# Xbee_Footprint_--_BLE_--_HM-10_--_Breako.net
KiCad netlist of a schematic drawn in EAGLE
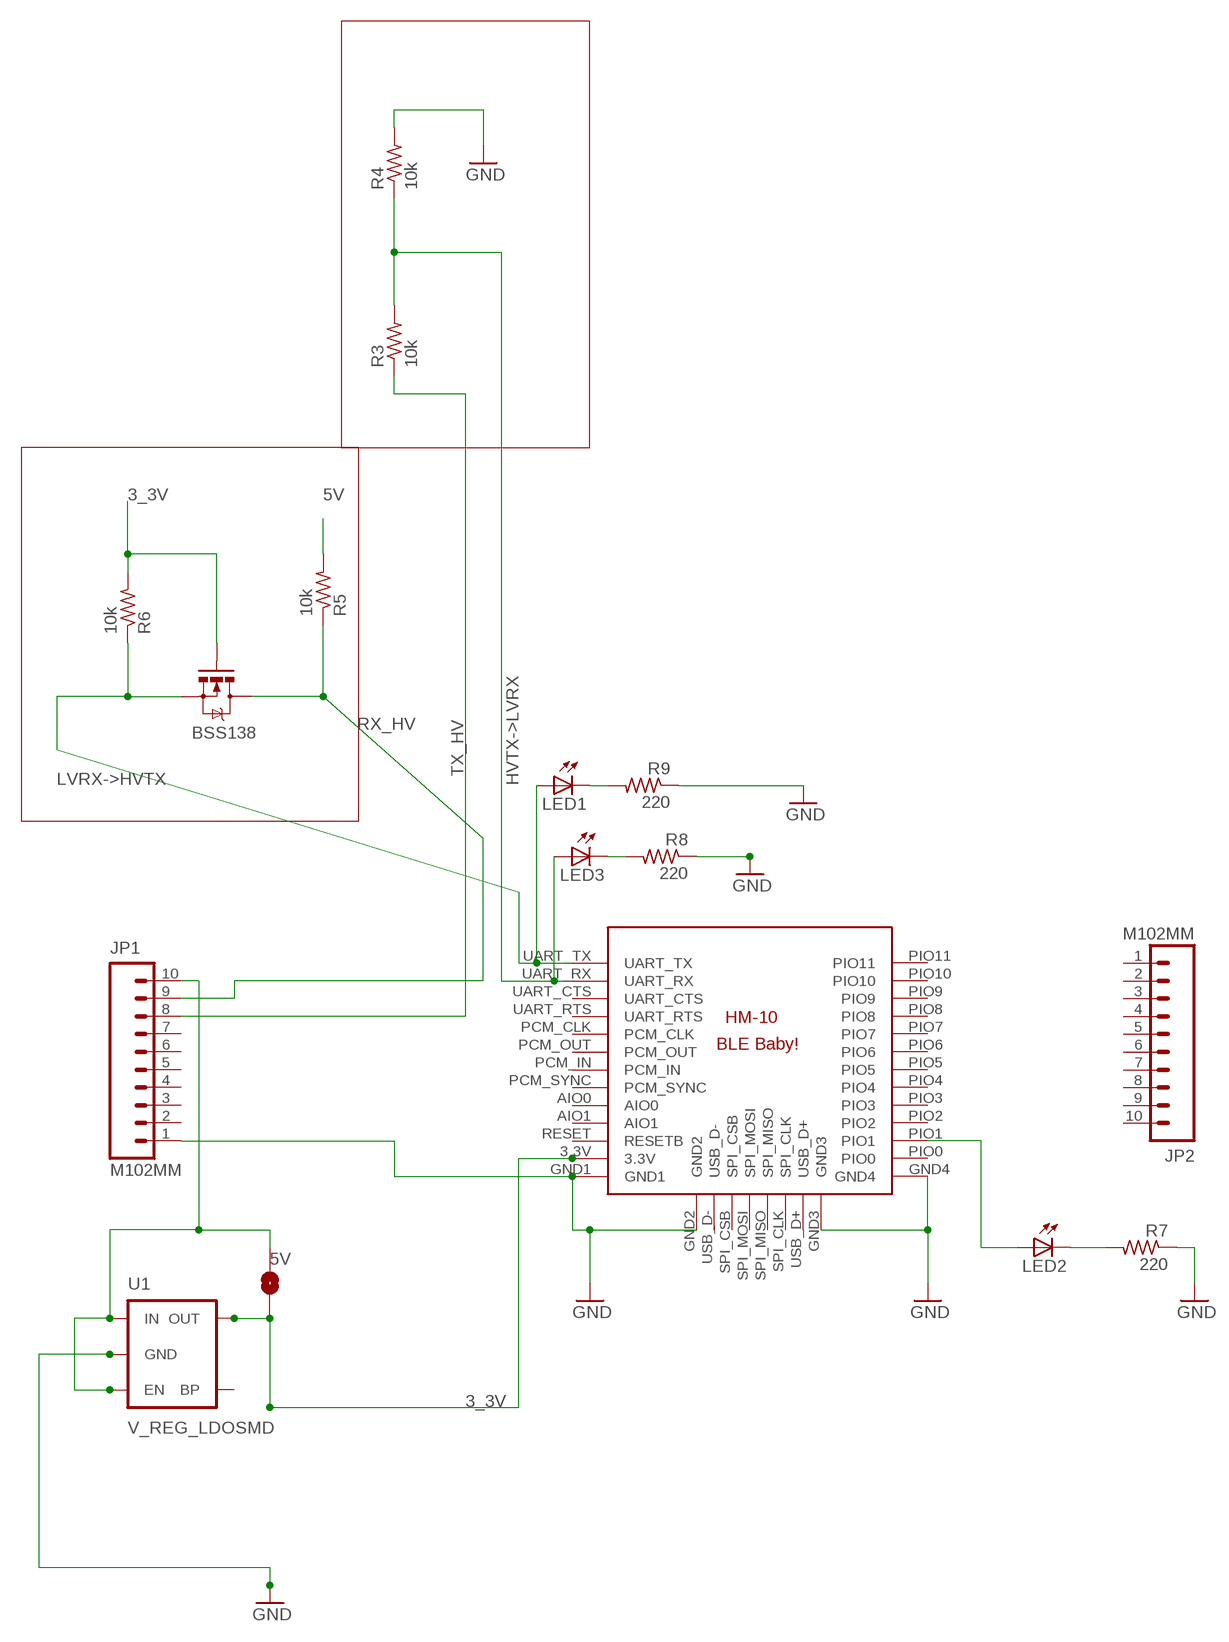
[diagram p0: schematic, sheet 1]

(export (version "E")
  (design (tool "Eeschema 10.0.6"))
  (components
    (comp (ref "BSS138")
      (value "MOSFET-NCHANNELSMD")
      (footprint "eagle-import:SOT23-3")
      (libsource (lib "eagle-import") (part "MOSFET-NCHANNELSMD"))
    )
    (comp (ref "JP1")
      (value "M102MM")
      (footprint "eagle-import:1X10-2MM")
      (libsource (lib "eagle-import") (part "M102MM"))
    )
    (comp (ref "JP2")
      (value "M102MM")
      (footprint "eagle-import:1X10-2MM")
      (libsource (lib "eagle-import") (part "M102MM"))
    )
    (comp (ref "LED1")
      (value "LED0603")
      (footprint "eagle-import:LED-0603")
      (libsource (lib "eagle-import") (part "LED0603"))
    )
    (comp (ref "LED2")
      (value "LED0603")
      (footprint "eagle-import:LED-0603")
      (libsource (lib "eagle-import") (part "LED0603"))
    )
    (comp (ref "LED3")
      (value "LED0603")
      (footprint "eagle-import:LED-0603")
      (libsource (lib "eagle-import") (part "LED0603"))
    )
    (comp (ref "R3")
      (value "10k")
      (footprint "eagle-import:M0805")
      (libsource (lib "eagle-import") (part "R-US_M0805"))
    )
    (comp (ref "R4")
      (value "10k")
      (footprint "eagle-import:M0805")
      (libsource (lib "eagle-import") (part "R-US_M0805"))
    )
    (comp (ref "R5")
      (value "10k")
      (footprint "eagle-import:M0805")
      (libsource (lib "eagle-import") (part "R-US_M0805"))
    )
    (comp (ref "R6")
      (value "10k")
      (footprint "eagle-import:M0805")
      (libsource (lib "eagle-import") (part "R-US_M0805"))
    )
    (comp (ref "R7")
      (value "220")
      (footprint "eagle-import:M0805")
      (libsource (lib "eagle-import") (part "R-US_M0805"))
    )
    (comp (ref "R8")
      (value "220")
      (footprint "eagle-import:M0805")
      (libsource (lib "eagle-import") (part "R-US_M0805"))
    )
    (comp (ref "R9")
      (value "220")
      (footprint "eagle-import:M0805")
      (libsource (lib "eagle-import") (part "R-US_M0805"))
    )
    (comp (ref "SJ1")
      (value "SOLDERJUMPERNO")
      (footprint "eagle-import:SJ_2S-NO")
      (libsource (lib "eagle-import") (part "SOLDERJUMPERNO"))
    )
    (comp (ref "U$1")
      (value "BLE-HM-10")
      (footprint "eagle-import:BLE-HM-10")
      (libsource (lib "eagle-import") (part "BLE-HM-10"))
    )
    (comp (ref "U1")
      (value "V_REG_LDOSMD")
      (footprint "eagle-import:SOT23-5")
      (libsource (lib "eagle-import") (part "V_REG_LDOSMD"))
    )
  )
  (nets
    (net (code "1") (name "/3_3V") (class "Default")
      (node (ref "BSS138") (pin "1") (pinfunction "G_1") (pintype "passive"))
      (node (ref "R6") (pin "2") (pinfunction "2_2") (pintype "passive"))
      (node (ref "SJ1") (pin "1") (pinfunction "1_1") (pintype "passive"))
      (node (ref "U$1") (pin "3.3V") (pinfunction "3.3V_3.3V") (pintype "bidirectional"))
      (node (ref "U1") (pin "5") (pinfunction "OUT_5") (pintype "passive"))
    )
    (net (code "2") (name "/5V") (class "Default")
      (node (ref "JP1") (pin "10") (pinfunction "10_10") (pintype "passive"))
      (node (ref "R5") (pin "2") (pinfunction "2_2") (pintype "passive"))
      (node (ref "SJ1") (pin "2") (pinfunction "2_2") (pintype "passive"))
      (node (ref "U1") (pin "1") (pinfunction "IN_1") (pintype "input"))
      (node (ref "U1") (pin "3") (pinfunction "EN_3") (pintype "input"))
    )
    (net (code "3") (name "/HVTX->LVRX") (class "Default")
      (node (ref "LED3") (pin "A") (pinfunction "A_A") (pintype "passive"))
      (node (ref "R3") (pin "2") (pinfunction "2_2") (pintype "passive"))
      (node (ref "R4") (pin "1") (pinfunction "1_1") (pintype "passive"))
      (node (ref "U$1") (pin "UART_RX") (pinfunction "UART_RX_UART_RX") (pintype "bidirectional"))
    )
    (net (code "4") (name "/LVRX->HVTX") (class "Default")
      (node (ref "BSS138") (pin "2") (pinfunction "S_2") (pintype "passive"))
      (node (ref "LED1") (pin "A") (pinfunction "A_A") (pintype "passive"))
      (node (ref "R6") (pin "1") (pinfunction "1_1") (pintype "passive"))
      (node (ref "U$1") (pin "UART_TX") (pinfunction "UART_TX_UART_TX") (pintype "bidirectional"))
    )
    (net (code "5") (name "/RX_HV") (class "Default")
      (node (ref "BSS138") (pin "3") (pinfunction "D_3") (pintype "passive"))
      (node (ref "JP1") (pin "9") (pinfunction "9_9") (pintype "passive"))
      (node (ref "R5") (pin "1") (pinfunction "1_1") (pintype "passive"))
    )
    (net (code "6") (name "/TX_HV") (class "Default")
      (node (ref "JP1") (pin "8") (pinfunction "8_8") (pintype "passive"))
      (node (ref "R3") (pin "1") (pinfunction "1_1") (pintype "passive"))
    )
    (net (code "7") (name "GND") (class "Default")
      (node (ref "JP1") (pin "1") (pinfunction "1_1") (pintype "passive"))
      (node (ref "R4") (pin "2") (pinfunction "2_2") (pintype "passive"))
      (node (ref "R7") (pin "1") (pinfunction "1_1") (pintype "passive"))
      (node (ref "R8") (pin "1") (pinfunction "1_1") (pintype "passive"))
      (node (ref "R9") (pin "1") (pinfunction "1_1") (pintype "passive"))
      (node (ref "U$1") (pin "GND1") (pinfunction "GND1_GND1") (pintype "bidirectional"))
      (node (ref "U$1") (pin "GND2") (pinfunction "GND2_GND2") (pintype "bidirectional"))
      (node (ref "U$1") (pin "GND3") (pinfunction "GND3_GND3") (pintype "bidirectional"))
      (node (ref "U$1") (pin "GND4") (pinfunction "GND4_GND4") (pintype "bidirectional"))
      (node (ref "U1") (pin "2") (pinfunction "GND_2") (pintype "input"))
    )
    (net (code "8") (name "Net-(LED1-PadC)") (class "Default")
      (node (ref "LED1") (pin "C") (pinfunction "C_C") (pintype "passive"))
      (node (ref "R9") (pin "2") (pinfunction "2_2") (pintype "passive"))
    )
    (net (code "9") (name "Net-(LED2-PadA)") (class "Default")
      (node (ref "LED2") (pin "A") (pinfunction "A_A") (pintype "passive"))
      (node (ref "U$1") (pin "PIO1") (pinfunction "PIO1_PIO1") (pintype "bidirectional"))
    )
    (net (code "10") (name "Net-(LED2-PadC)") (class "Default")
      (node (ref "LED2") (pin "C") (pinfunction "C_C") (pintype "passive"))
      (node (ref "R7") (pin "2") (pinfunction "2_2") (pintype "passive"))
    )
    (net (code "11") (name "Net-(LED3-PadC)") (class "Default")
      (node (ref "LED3") (pin "C") (pinfunction "C_C") (pintype "passive"))
      (node (ref "R8") (pin "2") (pinfunction "2_2") (pintype "passive"))
    )
    (net (code "12") (name "unconnected-(JP1-Pad2)") (class "Default")
      (node (ref "JP1") (pin "2") (pinfunction "2_2") (pintype "passive"))
    )
    (net (code "13") (name "unconnected-(JP1-Pad3)") (class "Default")
      (node (ref "JP1") (pin "3") (pinfunction "3_3") (pintype "passive"))
    )
    (net (code "14") (name "unconnected-(JP1-Pad4)") (class "Default")
      (node (ref "JP1") (pin "4") (pinfunction "4_4") (pintype "passive"))
    )
    (net (code "15") (name "unconnected-(JP1-Pad5)") (class "Default")
      (node (ref "JP1") (pin "5") (pinfunction "5_5") (pintype "passive"))
    )
    (net (code "16") (name "unconnected-(JP1-Pad6)") (class "Default")
      (node (ref "JP1") (pin "6") (pinfunction "6_6") (pintype "passive"))
    )
    (net (code "17") (name "unconnected-(JP1-Pad7)") (class "Default")
      (node (ref "JP1") (pin "7") (pinfunction "7_7") (pintype "passive"))
    )
    (net (code "18") (name "unconnected-(JP2-Pad1)") (class "Default")
      (node (ref "JP2") (pin "1") (pinfunction "1_1") (pintype "passive"))
    )
    (net (code "19") (name "unconnected-(JP2-Pad2)") (class "Default")
      (node (ref "JP2") (pin "2") (pinfunction "2_2") (pintype "passive"))
    )
    (net (code "20") (name "unconnected-(JP2-Pad3)") (class "Default")
      (node (ref "JP2") (pin "3") (pinfunction "3_3") (pintype "passive"))
    )
    (net (code "21") (name "unconnected-(JP2-Pad4)") (class "Default")
      (node (ref "JP2") (pin "4") (pinfunction "4_4") (pintype "passive"))
    )
    (net (code "22") (name "unconnected-(JP2-Pad5)") (class "Default")
      (node (ref "JP2") (pin "5") (pinfunction "5_5") (pintype "passive"))
    )
    (net (code "23") (name "unconnected-(JP2-Pad6)") (class "Default")
      (node (ref "JP2") (pin "6") (pinfunction "6_6") (pintype "passive"))
    )
    (net (code "24") (name "unconnected-(JP2-Pad7)") (class "Default")
      (node (ref "JP2") (pin "7") (pinfunction "7_7") (pintype "passive"))
    )
    (net (code "25") (name "unconnected-(JP2-Pad8)") (class "Default")
      (node (ref "JP2") (pin "8") (pinfunction "8_8") (pintype "passive"))
    )
    (net (code "26") (name "unconnected-(JP2-Pad9)") (class "Default")
      (node (ref "JP2") (pin "9") (pinfunction "9_9") (pintype "passive"))
    )
    (net (code "27") (name "unconnected-(JP2-Pad10)") (class "Default")
      (node (ref "JP2") (pin "10") (pinfunction "10_10") (pintype "passive"))
    )
    (net (code "28") (name "unconnected-(U$1-PadAIO0)") (class "Default")
      (node (ref "U$1") (pin "AIO0") (pinfunction "AIO0_AIO0") (pintype "bidirectional"))
    )
    (net (code "29") (name "unconnected-(U$1-PadAIO1)") (class "Default")
      (node (ref "U$1") (pin "AIO1") (pinfunction "AIO1_AIO1") (pintype "bidirectional"))
    )
    (net (code "30") (name "unconnected-(U$1-PadPCM_CLK)") (class "Default")
      (node (ref "U$1") (pin "PCM_CLK") (pinfunction "PCM_CLK_PCM_CLK") (pintype "bidirectional"))
    )
    (net (code "31") (name "unconnected-(U$1-PadPCM_IN)") (class "Default")
      (node (ref "U$1") (pin "PCM_IN") (pinfunction "PCM_IN_PCM_IN") (pintype "bidirectional"))
    )
    (net (code "32") (name "unconnected-(U$1-PadPCM_OUT)") (class "Default")
      (node (ref "U$1") (pin "PCM_OUT") (pinfunction "PCM_OUT_PCM_OUT") (pintype "bidirectional"))
    )
    (net (code "33") (name "unconnected-(U$1-PadPCM_SYNC)") (class "Default")
      (node (ref "U$1") (pin "PCM_SYNC") (pinfunction "PCM_SYNC_PCM_SYNC") (pintype "bidirectional"))
    )
    (net (code "34") (name "unconnected-(U$1-PadPIO0)") (class "Default")
      (node (ref "U$1") (pin "PIO0") (pinfunction "PIO0_PIO0") (pintype "bidirectional"))
    )
    (net (code "35") (name "unconnected-(U$1-PadPIO2)") (class "Default")
      (node (ref "U$1") (pin "PIO2") (pinfunction "PIO2_PIO2") (pintype "bidirectional"))
    )
    (net (code "36") (name "unconnected-(U$1-PadPIO3)") (class "Default")
      (node (ref "U$1") (pin "PIO3") (pinfunction "PIO3_PIO3") (pintype "bidirectional"))
    )
    (net (code "37") (name "unconnected-(U$1-PadPIO4)") (class "Default")
      (node (ref "U$1") (pin "PIO4") (pinfunction "PIO4_PIO4") (pintype "bidirectional"))
    )
    (net (code "38") (name "unconnected-(U$1-PadPIO5)") (class "Default")
      (node (ref "U$1") (pin "PIO5") (pinfunction "PIO5_PIO5") (pintype "bidirectional"))
    )
    (net (code "39") (name "unconnected-(U$1-PadPIO6)") (class "Default")
      (node (ref "U$1") (pin "PIO6") (pinfunction "PIO6_PIO6") (pintype "bidirectional"))
    )
    (net (code "40") (name "unconnected-(U$1-PadPIO7)") (class "Default")
      (node (ref "U$1") (pin "PIO7") (pinfunction "PIO7_PIO7") (pintype "bidirectional"))
    )
    (net (code "41") (name "unconnected-(U$1-PadPIO8)") (class "Default")
      (node (ref "U$1") (pin "PIO8") (pinfunction "PIO8_PIO8") (pintype "bidirectional"))
    )
    (net (code "42") (name "unconnected-(U$1-PadPIO9)") (class "Default")
      (node (ref "U$1") (pin "PIO9") (pinfunction "PIO9_PIO9") (pintype "bidirectional"))
    )
    (net (code "43") (name "unconnected-(U$1-PadPIO10)") (class "Default")
      (node (ref "U$1") (pin "PIO10") (pinfunction "PIO10_PIO10") (pintype "bidirectional"))
    )
    (net (code "44") (name "unconnected-(U$1-PadPIO11)") (class "Default")
      (node (ref "U$1") (pin "PIO11") (pinfunction "PIO11_PIO11") (pintype "bidirectional"))
    )
    (net (code "45") (name "unconnected-(U$1-PadSPI_CLK)") (class "Default")
      (node (ref "U$1") (pin "SPI_CLK") (pinfunction "SPI_CLK_SPI_CLK") (pintype "bidirectional"))
    )
    (net (code "46") (name "unconnected-(U$1-PadSPI_CSB)") (class "Default")
      (node (ref "U$1") (pin "SPI_CSB") (pinfunction "SPI_CSB_SPI_CSB") (pintype "bidirectional"))
    )
    (net (code "47") (name "unconnected-(U$1-PadSPI_MISO)") (class "Default")
      (node (ref "U$1") (pin "SPI_MISO") (pinfunction "SPI_MISO_SPI_MISO") (pintype "bidirectional"))
    )
    (net (code "48") (name "unconnected-(U$1-PadSPI_MOSI)") (class "Default")
      (node (ref "U$1") (pin "SPI_MOSI") (pinfunction "SPI_MOSI_SPI_MOSI") (pintype "bidirectional"))
    )
    (net (code "49") (name "unconnected-(U$1-PadUART_CTS)") (class "Default")
      (node (ref "U$1") (pin "UART_CTS") (pinfunction "UART_CTS_UART_CTS") (pintype "bidirectional"))
    )
    (net (code "50") (name "unconnected-(U$1-PadUART_RTS)") (class "Default")
      (node (ref "U$1") (pin "UART_RTS") (pinfunction "UART_RTS_UART_RTS") (pintype "bidirectional"))
    )
    (net (code "51") (name "unconnected-(U$1-PadUSB_D+)") (class "Default")
      (node (ref "U$1") (pin "USB_D+") (pinfunction "USB_D+_USB_D+") (pintype "bidirectional"))
    )
    (net (code "52") (name "unconnected-(U$1-PadUSB_D-)") (class "Default")
      (node (ref "U$1") (pin "USB_D-") (pinfunction "USB_D-_USB_D-") (pintype "bidirectional"))
    )
    (net (code "53") (name "unconnected-(U$1-RESETB-PadRESET)") (class "Default")
      (node (ref "U$1") (pin "RESET") (pinfunction "RESETB_RESET") (pintype "bidirectional"))
    )
    (net (code "54") (name "unconnected-(U1-BP-Pad4)") (class "Default")
      (node (ref "U1") (pin "4") (pinfunction "BP_4") (pintype "input"))
    )
  )
)
